# STC89C52RC.net
KiCad netlist of a schematic drawn in Altium Designer
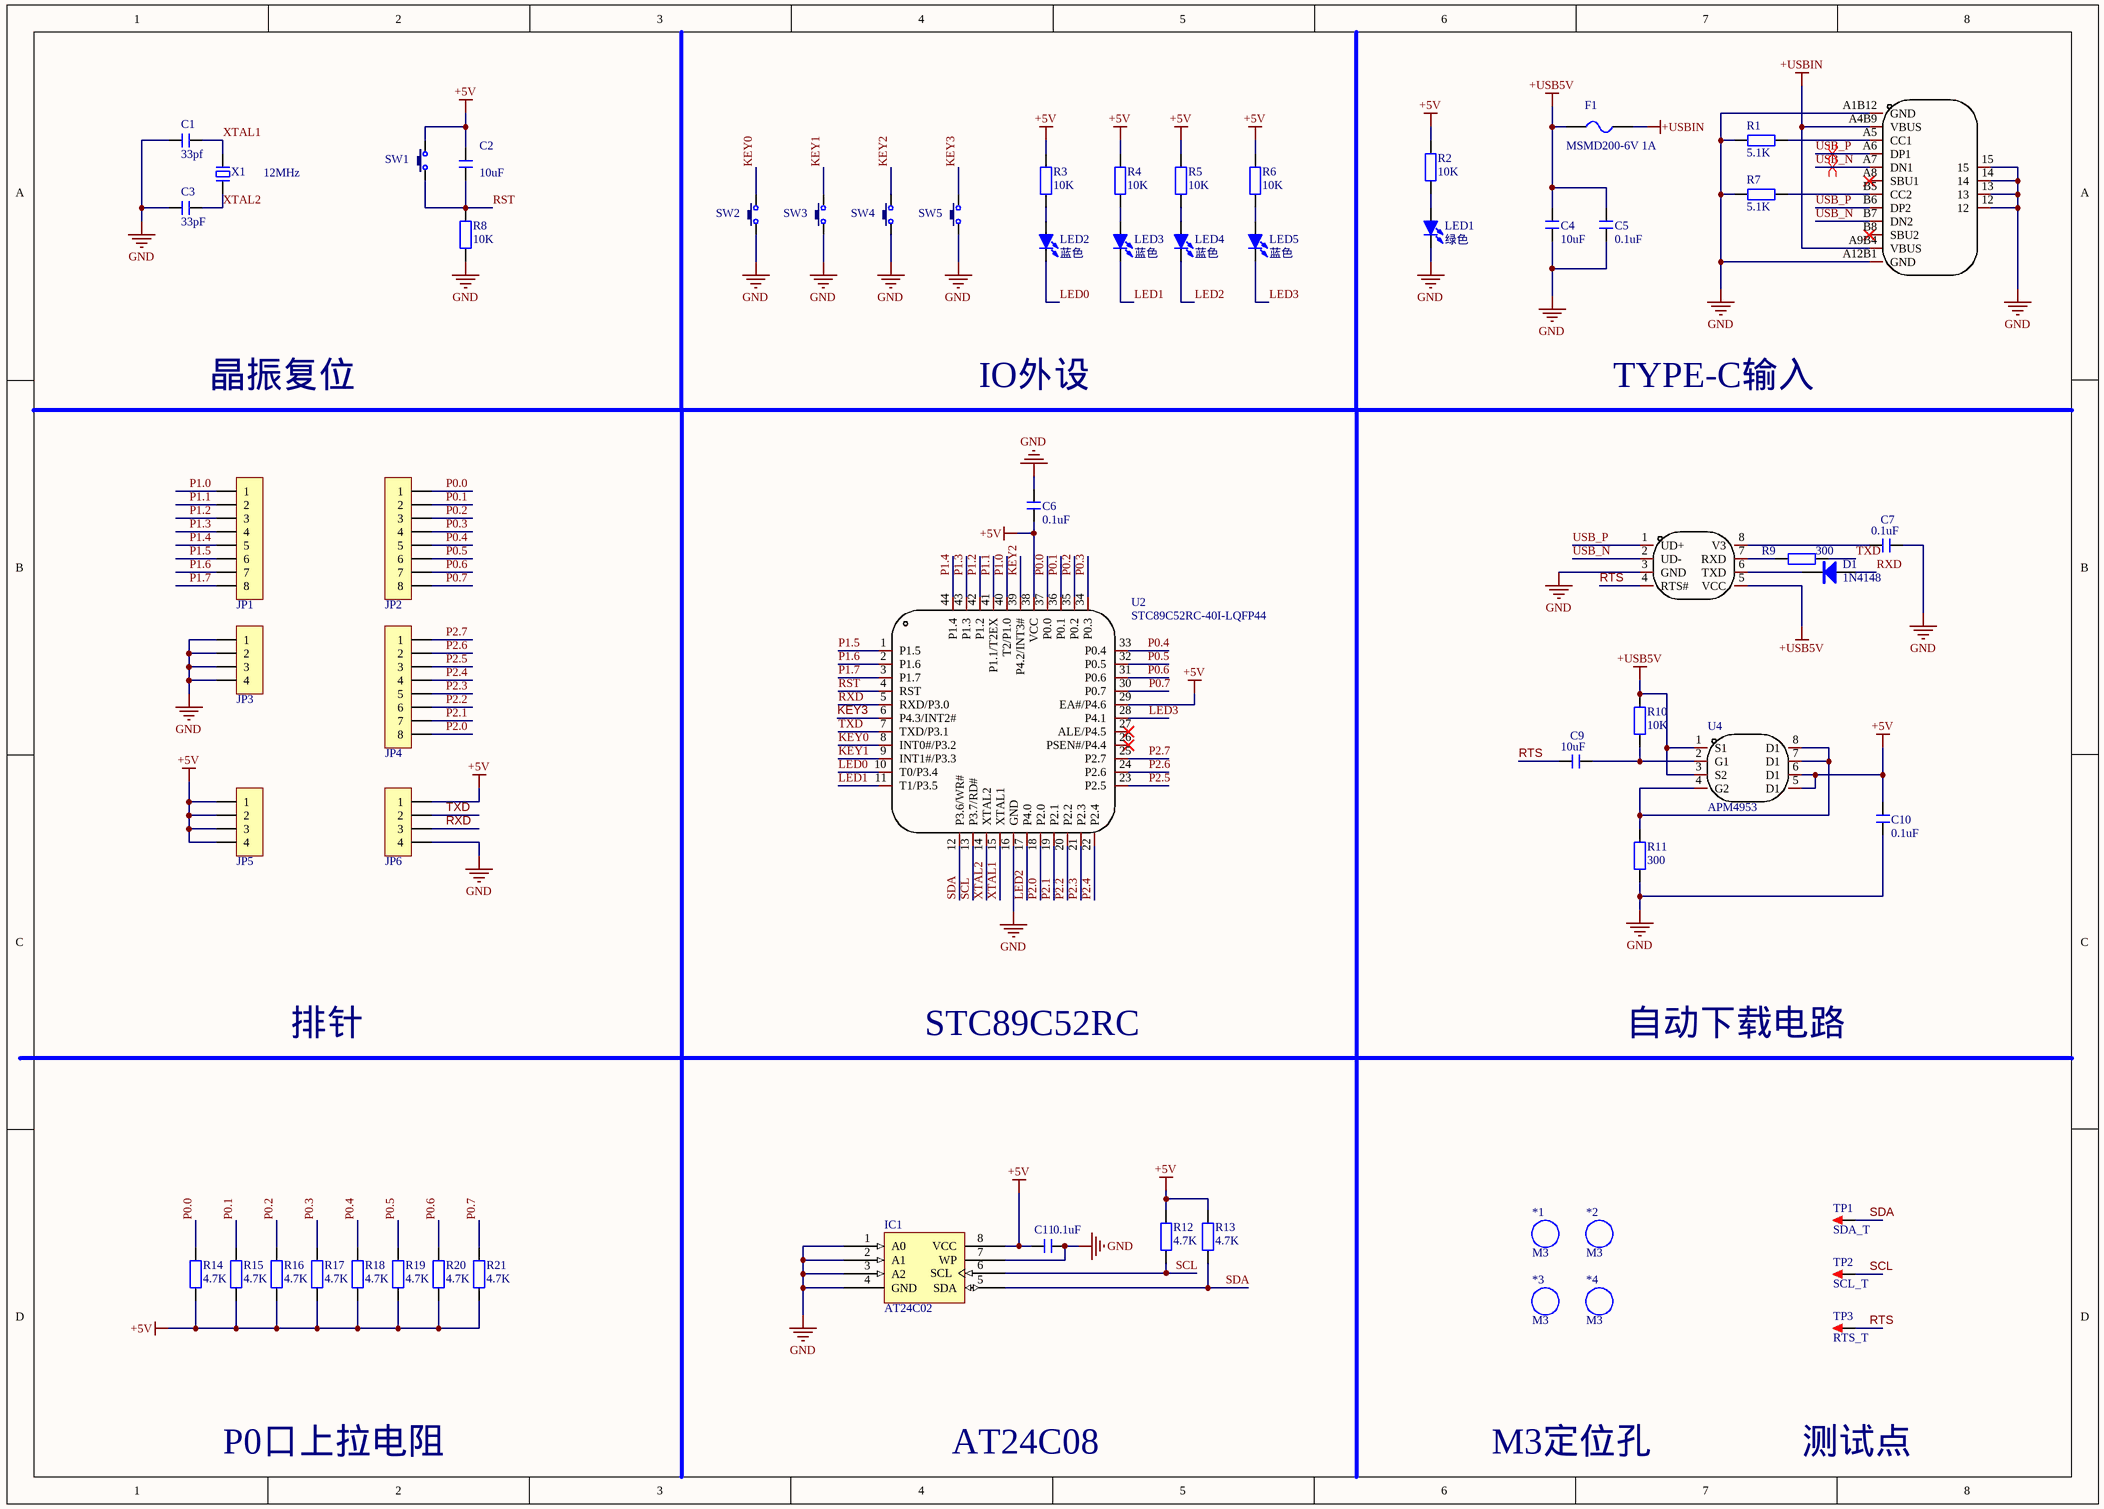
[diagram p0: STC89C52RC.SchDoc]

(export (version "E")
  (design (tool "Eeschema 10.0.6"))
  (components
    (comp (ref "*1")
      (value "M3")
      (footprint "M3 125X200")
      (description "铜柱孔")
      (fields (field (name "版权归属") "封装库来自淘宝 ID：黄晶宝石"))
      (libsource (lib "4.1 - 未分类器件") (part "M3"))
    )
    (comp (ref "*2")
      (value "M3")
      (footprint "M3 125X200")
      (description "铜柱孔")
      (fields (field (name "版权归属") "封装库来自淘宝 ID：黄晶宝石"))
      (libsource (lib "4.1 - 未分类器件") (part "M3"))
    )
    (comp (ref "*3")
      (value "M3")
      (footprint "M3 125X200")
      (description "铜柱孔")
      (fields (field (name "版权归属") "封装库来自淘宝 ID：黄晶宝石"))
      (libsource (lib "4.1 - 未分类器件") (part "M3"))
    )
    (comp (ref "*4")
      (value "M3")
      (footprint "M3 125X200")
      (description "铜柱孔")
      (fields (field (name "版权归属") "封装库来自淘宝 ID：黄晶宝石"))
      (libsource (lib "4.1 - 未分类器件") (part "M3"))
    )
    (comp (ref "C1")
      (value "33pf")
      (footprint "C 0805_L")
      (description "无极性贴片电容")
      (fields (field (name "版权归属") "源创客"))
      (libsource (lib "3.1   - 电阻-电容-电感") (part "C"))
    )
    (comp (ref "C2")
      (value "10uF")
      (footprint "C 0805_L")
      (description "无极性贴片电容")
      (fields (field (name "版权归属") "源创客"))
      (libsource (lib "3.1   - 电阻-电容-电感") (part "C"))
    )
    (comp (ref "C3")
      (value "33pF")
      (footprint "C 0805_L")
      (description "无极性贴片电容")
      (fields (field (name "版权归属") "源创客"))
      (libsource (lib "3.1   - 电阻-电容-电感") (part "C"))
    )
    (comp (ref "C4")
      (value "10uF")
      (footprint "C 0805_L")
      (description "无极性贴片电容")
      (fields (field (name "版权归属") "源创客"))
      (libsource (lib "3.1   - 电阻-电容-电感") (part "C"))
    )
    (comp (ref "C5")
      (value "0.1uF")
      (footprint "C 0805_L")
      (description "无极性贴片电容")
      (fields (field (name "版权归属") "源创客"))
      (libsource (lib "3.1   - 电阻-电容-电感") (part "C"))
    )
    (comp (ref "C6")
      (value "0.1uF")
      (footprint "C 0805_L")
      (description "无极性贴片电容")
      (fields (field (name "版权归属") "源创客"))
      (libsource (lib "3.1   - 电阻-电容-电感") (part "C"))
    )
    (comp (ref "C7")
      (value "0.1uF")
      (footprint "C 0805_L")
      (description "无极性贴片电容")
      (fields (field (name "版权归属") "源创客"))
      (libsource (lib "3.1   - 电阻-电容-电感") (part "C"))
    )
    (comp (ref "C9")
      (value "10uF")
      (footprint "C 0805_L")
      (description "无极性贴片电容")
      (fields (field (name "版权归属") "源创客"))
      (libsource (lib "3.1   - 电阻-电容-电感") (part "C"))
    )
    (comp (ref "C10")
      (value "0.1uF")
      (footprint "C 0805_L")
      (description "无极性贴片电容")
      (fields (field (name "版权归属") "源创客"))
      (libsource (lib "3.1   - 电阻-电容-电感") (part "C"))
    )
    (comp (ref "C11")
      (value "0.1uF")
      (footprint "C 0805_L")
      (description "无极性贴片电容")
      (fields (field (name "版权归属") "源创客"))
      (libsource (lib "3.1   - 电阻-电容-电感") (part "C"))
    )
    (comp (ref "D1")
      (value "1N4148")
      (footprint "SOD-323")
      (description "高速开关二极管")
      (fields (field (name "版权归属") "源创客"))
      (libsource (lib "8.1   - 二极管-整流桥") (part "1N4148"))
    )
    (comp (ref "F1")
      (value "MSMD200-6V 1A")
      (footprint "FU 0805")
      (description "贴片保险丝")
      (fields (field (name "版权归属") "封装库来自淘宝卖家 ID：黄晶宝石"))
      (libsource (lib "2.0 - 保险丝-晶振-光耦") (part "FU"))
    )
    (comp (ref "IC1")
      (value "AT24C02")
      (footprint "SOP8_N")
      (description "外置EEPROM")
      (fields (field (name "版权归属") "源创客"))
      (libsource (lib "1.1   - IC芯片") (part "24Cxx"))
    )
    (comp (ref "JP1")
      (value "HDR-1X8")
      (footprint "HDR2.54-LI-8P")
      (description "8P接插件")
      (fields (field (name "版权归属") "封装库来自淘宝 ID：黄晶宝石"))
      (libsource (lib "5.4 - 接插件-脚距2.54 (100mil) ") (part "Header 8"))
    )
    (comp (ref "JP2")
      (value "HDR-1X8")
      (footprint "HDR2.54-LI-8P")
      (description "8P接插件")
      (fields (field (name "版权归属") "封装库来自淘宝 ID：黄晶宝石"))
      (libsource (lib "") (part "Header 8_1"))
    )
    (comp (ref "JP3")
      (value "HDR-1X4")
      (footprint "HDR2.54-LI-4P")
      (description "4P接插件")
      (fields (field (name "版权归属") "封装库来自淘宝 ID：黄晶宝石"))
      (libsource (lib "") (part "Header 4_1"))
    )
    (comp (ref "JP4")
      (value "HDR-1X8")
      (footprint "HDR2.54-LI-8P")
      (description "8P接插件")
      (fields (field (name "版权归属") "封装库来自淘宝 ID：黄晶宝石"))
      (libsource (lib "") (part "Header 8_1"))
    )
    (comp (ref "JP5")
      (value "HDR-1X4")
      (footprint "HDR2.54-LI-4P")
      (description "4P接插件")
      (fields (field (name "版权归属") "封装库来自淘宝 ID：黄晶宝石"))
      (libsource (lib "") (part "Header 4_1"))
    )
    (comp (ref "JP6")
      (value "HDR-1X4")
      (footprint "HDR2.54-LI-4P")
      (description "4P接插件")
      (fields (field (name "版权归属") "封装库来自淘宝 ID：黄晶宝石"))
      (libsource (lib "5.4 - 接插件-脚距2.54 (100mil) ") (part "Header 4"))
    )
    (comp (ref "LED1")
      (value "绿色")
      (footprint "LED 0805G")
      (description "贴片LED")
      (fields (field (name "版权归属") "源创客"))
      (libsource (lib "9.1   - LED") (part "LED-SMD"))
    )
    (comp (ref "LED2")
      (value "蓝色")
      (footprint "LED 0805B")
      (description "贴片LED")
      (fields (field (name "版权归属") "源创客"))
      (libsource (lib "9.1   - LED") (part "LED-SMD"))
    )
    (comp (ref "LED3")
      (value "蓝色")
      (footprint "LED 0805B")
      (description "贴片LED")
      (fields (field (name "版权归属") "源创客"))
      (libsource (lib "9.1   - LED") (part "LED-SMD"))
    )
    (comp (ref "LED4")
      (value "蓝色")
      (footprint "LED 0805B")
      (description "贴片LED")
      (fields (field (name "版权归属") "源创客"))
      (libsource (lib "9.1   - LED") (part "LED-SMD"))
    )
    (comp (ref "LED5")
      (value "蓝色")
      (footprint "LED 0805B")
      (description "贴片LED")
      (fields (field (name "版权归属") "源创客"))
      (libsource (lib "9.1   - LED") (part "LED-SMD"))
    )
    (comp (ref "R1")
      (value "5.1K")
      (footprint "R 0805_L")
      (description "贴片电阻")
      (fields (field (name "版权归属") "源创客"))
      (libsource (lib "3.1   - 电阻-电容-电感") (part "R"))
    )
    (comp (ref "R2")
      (value "10K")
      (footprint "R 0805_L")
      (description "贴片电阻")
      (fields (field (name "版权归属") "源创客"))
      (libsource (lib "3.1   - 电阻-电容-电感") (part "R"))
    )
    (comp (ref "R3")
      (value "10K")
      (footprint "R 0805_L")
      (description "贴片电阻")
      (fields (field (name "版权归属") "源创客"))
      (libsource (lib "3.1   - 电阻-电容-电感") (part "R"))
    )
    (comp (ref "R4")
      (value "10K")
      (footprint "R 0805_L")
      (description "贴片电阻")
      (fields (field (name "版权归属") "源创客"))
      (libsource (lib "3.1   - 电阻-电容-电感") (part "R"))
    )
    (comp (ref "R5")
      (value "10K")
      (footprint "R 0805_L")
      (description "贴片电阻")
      (fields (field (name "版权归属") "源创客"))
      (libsource (lib "3.1   - 电阻-电容-电感") (part "R"))
    )
    (comp (ref "R6")
      (value "10K")
      (footprint "R 0805_L")
      (description "贴片电阻")
      (fields (field (name "版权归属") "源创客"))
      (libsource (lib "3.1   - 电阻-电容-电感") (part "R"))
    )
    (comp (ref "R7")
      (value "5.1K")
      (footprint "R 0805_L")
      (description "贴片电阻")
      (fields (field (name "版权归属") "源创客"))
      (libsource (lib "3.1   - 电阻-电容-电感") (part "R"))
    )
    (comp (ref "R8")
      (value "10K")
      (footprint "R 0805_L")
      (description "贴片电阻")
      (fields (field (name "版权归属") "源创客"))
      (libsource (lib "3.1   - 电阻-电容-电感") (part "R"))
    )
    (comp (ref "R9")
      (value "300")
      (footprint "R 0805_L")
      (description "贴片电阻")
      (fields (field (name "版权归属") "源创客"))
      (libsource (lib "3.1   - 电阻-电容-电感") (part "R"))
    )
    (comp (ref "R10")
      (value "10K")
      (footprint "R 0805_L")
      (description "贴片电阻")
      (fields (field (name "版权归属") "源创客"))
      (libsource (lib "3.1   - 电阻-电容-电感") (part "R"))
    )
    (comp (ref "R11")
      (value "300")
      (footprint "R 0805_L")
      (description "贴片电阻")
      (fields (field (name "版权归属") "源创客"))
      (libsource (lib "3.1   - 电阻-电容-电感") (part "R"))
    )
    (comp (ref "R12")
      (value "4.7K")
      (footprint "R 0805_L")
      (description "贴片电阻")
      (fields (field (name "版权归属") "源创客"))
      (libsource (lib "3.1   - 电阻-电容-电感") (part "R"))
    )
    (comp (ref "R13")
      (value "4.7K")
      (footprint "R 0805_L")
      (description "贴片电阻")
      (fields (field (name "版权归属") "源创客"))
      (libsource (lib "3.1   - 电阻-电容-电感") (part "R"))
    )
    (comp (ref "R14")
      (value "4.7K")
      (footprint "R 0805_L")
      (description "贴片电阻")
      (fields (field (name "版权归属") "源创客"))
      (libsource (lib "3.1   - 电阻-电容-电感") (part "R"))
    )
    (comp (ref "R15")
      (value "4.7K")
      (footprint "R 0805_L")
      (description "贴片电阻")
      (fields (field (name "版权归属") "源创客"))
      (libsource (lib "3.1   - 电阻-电容-电感") (part "R"))
    )
    (comp (ref "R16")
      (value "4.7K")
      (footprint "R 0805_L")
      (description "贴片电阻")
      (fields (field (name "版权归属") "源创客"))
      (libsource (lib "3.1   - 电阻-电容-电感") (part "R"))
    )
    (comp (ref "R17")
      (value "4.7K")
      (footprint "R 0805_L")
      (description "贴片电阻")
      (fields (field (name "版权归属") "源创客"))
      (libsource (lib "3.1   - 电阻-电容-电感") (part "R"))
    )
    (comp (ref "R18")
      (value "4.7K")
      (footprint "R 0805_L")
      (description "贴片电阻")
      (fields (field (name "版权归属") "源创客"))
      (libsource (lib "3.1   - 电阻-电容-电感") (part "R"))
    )
    (comp (ref "R19")
      (value "4.7K")
      (footprint "R 0805_L")
      (description "贴片电阻")
      (fields (field (name "版权归属") "源创客"))
      (libsource (lib "3.1   - 电阻-电容-电感") (part "R"))
    )
    (comp (ref "R20")
      (value "4.7K")
      (footprint "R 0805_L")
      (description "贴片电阻")
      (fields (field (name "版权归属") "源创客"))
      (libsource (lib "3.1   - 电阻-电容-电感") (part "R"))
    )
    (comp (ref "R21")
      (value "4.7K")
      (footprint "R 0805_L")
      (description "贴片电阻")
      (fields (field (name "版权归属") "源创客"))
      (libsource (lib "3.1   - 电阻-电容-电感") (part "R"))
    )
    (comp (ref "SW1")
      (value "3x6x5")
      (footprint "TSW SMD-3*6*2.5")
      (description "3x6轻触开关")
      (fields (field (name "版权归属") "源创客"))
      (libsource (lib "5.1   - 按键-开关") (part "TSW 3x6"))
    )
    (comp (ref "SW2")
      (value "3x6x5")
      (footprint "TSW SMD-3*6*2.5")
      (description "3x6轻触开关")
      (fields (field (name "版权归属") "源创客"))
      (libsource (lib "5.1   - 按键-开关") (part "TSW 3x6"))
    )
    (comp (ref "SW3")
      (value "3x6x5")
      (footprint "TSW SMD-3*6*2.5")
      (description "3x6轻触开关")
      (fields (field (name "版权归属") "源创客"))
      (libsource (lib "5.1   - 按键-开关") (part "TSW 3x6"))
    )
    (comp (ref "SW4")
      (value "3x6x5")
      (footprint "TSW SMD-3*6*2.5")
      (description "3x6轻触开关")
      (fields (field (name "版权归属") "源创客"))
      (libsource (lib "5.1   - 按键-开关") (part "TSW 3x6"))
    )
    (comp (ref "SW5")
      (value "3x6x5")
      (footprint "TSW SMD-3*6*2.5")
      (description "3x6轻触开关")
      (fields (field (name "版权归属") "源创客"))
      (libsource (lib "5.1   - 按键-开关") (part "TSW 3x6"))
    )
    (comp (ref "TP1")
      (value "SDA_T")
      (footprint "TEST 1.2")
      (description "测试点")
      (fields (field (name "版权归属") "封装库来自淘宝 ID：黄晶宝石"))
      (libsource (lib "4.1 - 未分类器件") (part "TEST"))
    )
    (comp (ref "TP2")
      (value "SCL_T")
      (footprint "TEST 1.2")
      (description "测试点")
      (fields (field (name "版权归属") "封装库来自淘宝 ID：黄晶宝石"))
      (libsource (lib "4.1 - 未分类器件") (part "TEST"))
    )
    (comp (ref "TP3")
      (value "RTS_T")
      (footprint "TEST 1.2")
      (description "测试点")
      (fields (field (name "版权归属") "封装库来自淘宝 ID：黄晶宝石"))
      (libsource (lib "4.1 - 未分类器件") (part "TEST"))
    )
    (comp (ref "U1")
      (value "YTC-TC16S-24")
      (footprint "USB-C-SMD_YTC-TC16S-24")
      (fields (field (name "MANUFACTURER") "YIYUAN(怡远)"))
      (libsource (lib "Type-C16S-24") (part "YTC-TC16S-24"))
    )
    (comp (ref "U2")
      (value "STC89C52RC")
      (footprint "LQFP44 10X10_N")
      (description "CPU内核:51系列;CPU最大主频:-;程序存储容量:8KB;程序存储器类型:FLASH;RAM总容量:512Byte;GPIO端口数量:39;")
      (fields
        (field (name "NAME") "STC89C52RC-40I-LQFP44")
        (field (name "MANUFACTURER") "STC(宏晶)")
        (field (name "MANUFACTURER PART") "STC89C52RC-40I-LQFP44")
      )
      (libsource (lib "altium-import") (part "root_0_STC89C52RC-40I-LQFP44_"))
    )
    (comp (ref "U3")
      (value "CH340N")
      (footprint "SOP8_L")
      (fields (field (name "MANUFACTURER") "WCH(南京沁恒)"))
      (libsource (lib "CH340N") (part "CH340N"))
    )
    (comp (ref "U4")
      (value "APM4953")
      (footprint "SOP8")
      (description "场效应管")
      (libsource (lib "STC89C52RC") (part "APM4953"))
    )
    (comp (ref "X1")
      (value "12MHz")
      (footprint "OSC 5032-2P")
      (description "2脚无源脚晶振")
      (fields (field (name "版权归属") "源创客"))
      (libsource (lib "10.1 - 保险丝-晶振") (part "XTAL-2P"))
    )
  )
  (nets
    (net (code "1") (name "+5V") (class "Default")
      (node (ref "C10") (pin "1") (pinfunction "1_1") (pintype "passive"))
      (node (ref "C11") (pin "1") (pinfunction "1_1") (pintype "passive"))
      (node (ref "C2") (pin "1") (pinfunction "1_1") (pintype "passive"))
      (node (ref "C6") (pin "2") (pinfunction "2_2") (pintype "passive"))
      (node (ref "IC1") (pin "8") (pinfunction "VCC_8") (pintype "power_in"))
      (node (ref "JP5") (pin "1") (pinfunction "1_1") (pintype "passive"))
      (node (ref "JP5") (pin "2") (pinfunction "2_2") (pintype "passive"))
      (node (ref "JP5") (pin "3") (pinfunction "3_3") (pintype "passive"))
      (node (ref "JP5") (pin "4") (pinfunction "4_4") (pintype "passive"))
      (node (ref "JP6") (pin "1") (pinfunction "1_1") (pintype "passive"))
      (node (ref "R12") (pin "2") (pinfunction "2_2") (pintype "passive"))
      (node (ref "R13") (pin "2") (pinfunction "2_2") (pintype "passive"))
      (node (ref "R14") (pin "1") (pinfunction "1_1") (pintype "passive"))
      (node (ref "R15") (pin "1") (pinfunction "1_1") (pintype "passive"))
      (node (ref "R16") (pin "1") (pinfunction "1_1") (pintype "passive"))
      (node (ref "R17") (pin "1") (pinfunction "1_1") (pintype "passive"))
      (node (ref "R18") (pin "1") (pinfunction "1_1") (pintype "passive"))
      (node (ref "R19") (pin "1") (pinfunction "1_1") (pintype "passive"))
      (node (ref "R2") (pin "2") (pinfunction "2_2") (pintype "passive"))
      (node (ref "R20") (pin "1") (pinfunction "1_1") (pintype "passive"))
      (node (ref "R21") (pin "1") (pinfunction "1_1") (pintype "passive"))
      (node (ref "R3") (pin "2") (pinfunction "2_2") (pintype "passive"))
      (node (ref "R4") (pin "2") (pinfunction "2_2") (pintype "passive"))
      (node (ref "R5") (pin "2") (pinfunction "2_2") (pintype "passive"))
      (node (ref "R6") (pin "2") (pinfunction "2_2") (pintype "passive"))
      (node (ref "SW1") (pin "2") (pinfunction "2_2") (pintype "passive"))
      (node (ref "U2") (pin "29") (pinfunction "EA#/P4.6_29") (pintype "passive"))
      (node (ref "U2") (pin "38") (pinfunction "VCC_38") (pintype "passive"))
      (node (ref "U4") (pin "5") (pinfunction "D1_5") (pintype "passive"))
      (node (ref "U4") (pin "6") (pinfunction "D1_6") (pintype "passive"))
    )
    (net (code "2") (name "+USB5V") (class "Default")
      (node (ref "C4") (pin "2") (pinfunction "2_2") (pintype "passive"))
      (node (ref "C5") (pin "2") (pinfunction "2_2") (pintype "passive"))
      (node (ref "F1") (pin "1") (pinfunction "1_1") (pintype "passive"))
      (node (ref "R10") (pin "2") (pinfunction "2_2") (pintype "passive"))
      (node (ref "U3") (pin "5") (pinfunction "VCC_5") (pintype "passive"))
      (node (ref "U4") (pin "1") (pinfunction "S1_1") (pintype "passive"))
      (node (ref "U4") (pin "3") (pinfunction "S2_3") (pintype "passive"))
    )
    (net (code "3") (name "+USBIN") (class "Default")
      (node (ref "F1") (pin "2") (pinfunction "2_2") (pintype "passive"))
      (node (ref "U1") (pin "A4B9") (pinfunction "VBUS_A4B9") (pintype "passive"))
      (node (ref "U1") (pin "A9B4") (pinfunction "VBUS_A9B4") (pintype "passive"))
    )
    (net (code "4") (name "/KEY0") (class "Default")
      (node (ref "SW2") (pin "2") (pinfunction "2_2") (pintype "passive"))
      (node (ref "U2") (pin "8") (pinfunction "INT0#/P3.2_8") (pintype "passive"))
    )
    (net (code "5") (name "/KEY1") (class "Default")
      (node (ref "SW3") (pin "2") (pinfunction "2_2") (pintype "passive"))
      (node (ref "U2") (pin "9") (pinfunction "INT1#/P3.3_9") (pintype "passive"))
    )
    (net (code "6") (name "/KEY2") (class "Default")
      (node (ref "SW4") (pin "2") (pinfunction "2_2") (pintype "passive"))
      (node (ref "U2") (pin "39") (pinfunction "P4.2/INT3#_39") (pintype "passive"))
    )
    (net (code "7") (name "/KEY3") (class "Default")
      (node (ref "SW5") (pin "2") (pinfunction "2_2") (pintype "passive"))
      (node (ref "U2") (pin "6") (pinfunction "P4.3/INT2#_6") (pintype "passive"))
    )
    (net (code "8") (name "/LED0") (class "Default")
      (node (ref "LED2") (pin "2") (pinfunction "K_2") (pintype "passive"))
      (node (ref "U2") (pin "10") (pinfunction "T0/P3.4_10") (pintype "passive"))
    )
    (net (code "9") (name "/LED1") (class "Default")
      (node (ref "LED3") (pin "2") (pinfunction "K_2") (pintype "passive"))
      (node (ref "U2") (pin "11") (pinfunction "T1/P3.5_11") (pintype "passive"))
    )
    (net (code "10") (name "/LED2") (class "Default")
      (node (ref "LED4") (pin "2") (pinfunction "K_2") (pintype "passive"))
      (node (ref "U2") (pin "17") (pinfunction "P4.0_17") (pintype "passive"))
    )
    (net (code "11") (name "/LED3") (class "Default")
      (node (ref "LED5") (pin "2") (pinfunction "K_2") (pintype "passive"))
      (node (ref "U2") (pin "28") (pinfunction "P4.1_28") (pintype "passive"))
    )
    (net (code "12") (name "/P0.0") (class "Default")
      (node (ref "JP2") (pin "1") (pinfunction "1_1") (pintype "passive"))
      (node (ref "R14") (pin "2") (pinfunction "2_2") (pintype "passive"))
      (node (ref "U2") (pin "37") (pinfunction "P0.0_37") (pintype "passive"))
    )
    (net (code "13") (name "/P0.1") (class "Default")
      (node (ref "JP2") (pin "2") (pinfunction "2_2") (pintype "passive"))
      (node (ref "R15") (pin "2") (pinfunction "2_2") (pintype "passive"))
      (node (ref "U2") (pin "36") (pinfunction "P0.1_36") (pintype "passive"))
    )
    (net (code "14") (name "/P0.2") (class "Default")
      (node (ref "JP2") (pin "3") (pinfunction "3_3") (pintype "passive"))
      (node (ref "R16") (pin "2") (pinfunction "2_2") (pintype "passive"))
      (node (ref "U2") (pin "35") (pinfunction "P0.2_35") (pintype "passive"))
    )
    (net (code "15") (name "/P0.3") (class "Default")
      (node (ref "JP2") (pin "4") (pinfunction "4_4") (pintype "passive"))
      (node (ref "R17") (pin "2") (pinfunction "2_2") (pintype "passive"))
      (node (ref "U2") (pin "34") (pinfunction "P0.3_34") (pintype "passive"))
    )
    (net (code "16") (name "/P0.4") (class "Default")
      (node (ref "JP2") (pin "5") (pinfunction "5_5") (pintype "passive"))
      (node (ref "R18") (pin "2") (pinfunction "2_2") (pintype "passive"))
      (node (ref "U2") (pin "33") (pinfunction "P0.4_33") (pintype "passive"))
    )
    (net (code "17") (name "/P0.5") (class "Default")
      (node (ref "JP2") (pin "6") (pinfunction "6_6") (pintype "passive"))
      (node (ref "R19") (pin "2") (pinfunction "2_2") (pintype "passive"))
      (node (ref "U2") (pin "32") (pinfunction "P0.5_32") (pintype "passive"))
    )
    (net (code "18") (name "/P0.6") (class "Default")
      (node (ref "JP2") (pin "7") (pinfunction "7_7") (pintype "passive"))
      (node (ref "R20") (pin "2") (pinfunction "2_2") (pintype "passive"))
      (node (ref "U2") (pin "31") (pinfunction "P0.6_31") (pintype "passive"))
    )
    (net (code "19") (name "/P0.7") (class "Default")
      (node (ref "JP2") (pin "8") (pinfunction "8_8") (pintype "passive"))
      (node (ref "R21") (pin "2") (pinfunction "2_2") (pintype "passive"))
      (node (ref "U2") (pin "30") (pinfunction "P0.7_30") (pintype "passive"))
    )
    (net (code "20") (name "/P1.0") (class "Default")
      (node (ref "JP1") (pin "1") (pinfunction "1_1") (pintype "passive"))
      (node (ref "U2") (pin "40") (pinfunction "T2/P1.0_40") (pintype "passive"))
    )
    (net (code "21") (name "/P1.1") (class "Default")
      (node (ref "JP1") (pin "2") (pinfunction "2_2") (pintype "passive"))
      (node (ref "U2") (pin "41") (pinfunction "P1.1/T2EX_41") (pintype "passive"))
    )
    (net (code "22") (name "/P1.2") (class "Default")
      (node (ref "JP1") (pin "3") (pinfunction "3_3") (pintype "passive"))
      (node (ref "U2") (pin "42") (pinfunction "P1.2_42") (pintype "passive"))
    )
    (net (code "23") (name "/P1.3") (class "Default")
      (node (ref "JP1") (pin "4") (pinfunction "4_4") (pintype "passive"))
      (node (ref "U2") (pin "43") (pinfunction "P1.3_43") (pintype "passive"))
    )
    (net (code "24") (name "/P1.4") (class "Default")
      (node (ref "JP1") (pin "5") (pinfunction "5_5") (pintype "passive"))
      (node (ref "U2") (pin "44") (pinfunction "P1.4_44") (pintype "passive"))
    )
    (net (code "25") (name "/P1.5") (class "Default")
      (node (ref "JP1") (pin "6") (pinfunction "6_6") (pintype "passive"))
      (node (ref "U2") (pin "1") (pinfunction "P1.5_1") (pintype "passive"))
    )
    (net (code "26") (name "/P1.6") (class "Default")
      (node (ref "JP1") (pin "7") (pinfunction "7_7") (pintype "passive"))
      (node (ref "U2") (pin "2") (pinfunction "P1.6_2") (pintype "passive"))
    )
    (net (code "27") (name "/P1.7") (class "Default")
      (node (ref "JP1") (pin "8") (pinfunction "8_8") (pintype "passive"))
      (node (ref "U2") (pin "3") (pinfunction "P1.7_3") (pintype "passive"))
    )
    (net (code "28") (name "/P2.0") (class "Default")
      (node (ref "JP4") (pin "8") (pinfunction "8_8") (pintype "passive"))
      (node (ref "U2") (pin "18") (pinfunction "P2.0_18") (pintype "passive"))
    )
    (net (code "29") (name "/P2.1") (class "Default")
      (node (ref "JP4") (pin "7") (pinfunction "7_7") (pintype "passive"))
      (node (ref "U2") (pin "19") (pinfunction "P2.1_19") (pintype "passive"))
    )
    (net (code "30") (name "/P2.2") (class "Default")
      (node (ref "JP4") (pin "6") (pinfunction "6_6") (pintype "passive"))
      (node (ref "U2") (pin "20") (pinfunction "P2.2_20") (pintype "passive"))
    )
    (net (code "31") (name "/P2.3") (class "Default")
      (node (ref "JP4") (pin "5") (pinfunction "5_5") (pintype "passive"))
      (node (ref "U2") (pin "21") (pinfunction "P2.3_21") (pintype "passive"))
    )
    (net (code "32") (name "/P2.4") (class "Default")
      (node (ref "JP4") (pin "4") (pinfunction "4_4") (pintype "passive"))
      (node (ref "U2") (pin "22") (pinfunction "P2.4_22") (pintype "passive"))
    )
    (net (code "33") (name "/P2.5") (class "Default")
      (node (ref "JP4") (pin "3") (pinfunction "3_3") (pintype "passive"))
      (node (ref "U2") (pin "23") (pinfunction "P2.5_23") (pintype "passive"))
    )
    (net (code "34") (name "/P2.6") (class "Default")
      (node (ref "JP4") (pin "2") (pinfunction "2_2") (pintype "passive"))
      (node (ref "U2") (pin "24") (pinfunction "P2.6_24") (pintype "passive"))
    )
    (net (code "35") (name "/P2.7") (class "Default")
      (node (ref "JP4") (pin "1") (pinfunction "1_1") (pintype "passive"))
      (node (ref "U2") (pin "25") (pinfunction "P2.7_25") (pintype "passive"))
    )
    (net (code "36") (name "/RST") (class "Default")
      (node (ref "C2") (pin "2") (pinfunction "2_2") (pintype "passive"))
      (node (ref "R8") (pin "2") (pinfunction "2_2") (pintype "passive"))
      (node (ref "SW1") (pin "1") (pinfunction "1_1") (pintype "passive"))
      (node (ref "U2") (pin "4") (pinfunction "RST_4") (pintype "passive"))
    )
    (net (code "37") (name "/RTS") (class "Default")
      (node (ref "C9") (pin "1") (pinfunction "1_1") (pintype "passive"))
      (node (ref "TP3") (pin "1") (pinfunction "1_1") (pintype "passive"))
      (node (ref "U3") (pin "4") (pinfunction "RTS#_4") (pintype "passive"))
    )
    (net (code "38") (name "/RXD") (class "Default")
      (node (ref "D1") (pin "1") (pinfunction "A_1") (pintype "passive"))
      (node (ref "JP6") (pin "3") (pinfunction "3_3") (pintype "passive"))
      (node (ref "U2") (pin "5") (pinfunction "RXD/P3.0_5") (pintype "passive"))
    )
    (net (code "39") (name "/SCL") (class "Default")
      (node (ref "IC1") (pin "6") (pinfunction "SCL_6") (pintype "input"))
      (node (ref "R12") (pin "1") (pinfunction "1_1") (pintype "passive"))
      (node (ref "TP2") (pin "1") (pinfunction "1_1") (pintype "passive"))
      (node (ref "U2") (pin "13") (pinfunction "P3.7/RD#_13") (pintype "passive"))
    )
    (net (code "40") (name "/SDA") (class "Default")
      (node (ref "IC1") (pin "5") (pinfunction "SDA_5") (pintype "bidirectional"))
      (node (ref "R13") (pin "1") (pinfunction "1_1") (pintype "passive"))
      (node (ref "TP1") (pin "1") (pinfunction "1_1") (pintype "passive"))
      (node (ref "U2") (pin "12") (pinfunction "P3.6/WR#_12") (pintype "passive"))
    )
    (net (code "41") (name "/TXD") (class "Default")
      (node (ref "JP6") (pin "2") (pinfunction "2_2") (pintype "passive"))
      (node (ref "R9") (pin "2") (pinfunction "2_2") (pintype "passive"))
      (node (ref "U2") (pin "7") (pinfunction "TXD/P3.1_7") (pintype "passive"))
    )
    (net (code "42") (name "/USB_N") (class "Default")
      (node (ref "U1") (pin "A7") (pinfunction "DN1_A7") (pintype "passive"))
      (node (ref "U1") (pin "B7") (pinfunction "DN2_B7") (pintype "passive"))
      (node (ref "U3") (pin "2") (pinfunction "UD-_2") (pintype "passive"))
    )
    (net (code "43") (name "/USB_P") (class "Default")
      (node (ref "U1") (pin "A6") (pinfunction "DP1_A6") (pintype "passive"))
      (node (ref "U1") (pin "B6") (pinfunction "DP2_B6") (pintype "passive"))
      (node (ref "U3") (pin "1") (pinfunction "UD+_1") (pintype "passive"))
    )
    (net (code "44") (name "/XTAL1") (class "Default")
      (node (ref "C1") (pin "1") (pinfunction "1_1") (pintype "passive"))
      (node (ref "U2") (pin "15") (pinfunction "XTAL1_15") (pintype "passive"))
      (node (ref "X1") (pin "1") (pinfunction "1_1") (pintype "passive"))
    )
    (net (code "45") (name "/XTAL2") (class "Default")
      (node (ref "C3") (pin "1") (pinfunction "1_1") (pintype "passive"))
      (node (ref "U2") (pin "14") (pinfunction "XTAL2_14") (pintype "passive"))
      (node (ref "X1") (pin "2") (pinfunction "2_2") (pintype "passive"))
    )
    (net (code "46") (name "GND") (class "Default")
      (node (ref "C1") (pin "2") (pinfunction "2_2") (pintype "passive"))
      (node (ref "C10") (pin "2") (pinfunction "2_2") (pintype "passive"))
      (node (ref "C11") (pin "2") (pinfunction "2_2") (pintype "passive"))
      (node (ref "C3") (pin "2") (pinfunction "2_2") (pintype "passive"))
      (node (ref "C4") (pin "1") (pinfunction "1_1") (pintype "passive"))
      (node (ref "C5") (pin "1") (pinfunction "1_1") (pintype "passive"))
      (node (ref "C6") (pin "1") (pinfunction "1_1") (pintype "passive"))
      (node (ref "C7") (pin "2") (pinfunction "2_2") (pintype "passive"))
      (node (ref "IC1") (pin "1") (pinfunction "A0_1") (pintype "input"))
      (node (ref "IC1") (pin "2") (pinfunction "A1_2") (pintype "input"))
      (node (ref "IC1") (pin "3") (pinfunction "A2_3") (pintype "input"))
      (node (ref "IC1") (pin "4") (pinfunction "GND_4") (pintype "passive"))
      (node (ref "IC1") (pin "7") (pinfunction "WP_7") (pintype "passive"))
      (node (ref "JP3") (pin "1") (pinfunction "1_1") (pintype "passive"))
      (node (ref "JP3") (pin "2") (pinfunction "2_2") (pintype "passive"))
      (node (ref "JP3") (pin "3") (pinfunction "3_3") (pintype "passive"))
      (node (ref "JP3") (pin "4") (pinfunction "4_4") (pintype "passive"))
      (node (ref "JP6") (pin "4") (pinfunction "4_4") (pintype "passive"))
      (node (ref "LED1") (pin "2") (pinfunction "K_2") (pintype "passive"))
      (node (ref "R1") (pin "1") (pinfunction "1_1") (pintype "passive"))
      (node (ref "R11") (pin "1") (pinfunction "1_1") (pintype "passive"))
      (node (ref "R7") (pin "1") (pinfunction "1_1") (pintype "passive"))
      (node (ref "R8") (pin "1") (pinfunction "1_1") (pintype "passive"))
      (node (ref "SW2") (pin "1") (pinfunction "1_1") (pintype "passive"))
      (node (ref "SW3") (pin "1") (pinfunction "1_1") (pintype "passive"))
      (node (ref "SW4") (pin "1") (pinfunction "1_1") (pintype "passive"))
      (node (ref "SW5") (pin "1") (pinfunction "1_1") (pintype "passive"))
      (node (ref "U1") (pin "12") (pinfunction "12_12") (pintype "passive"))
      (node (ref "U1") (pin "13") (pinfunction "13_13") (pintype "passive"))
      (node (ref "U1") (pin "14") (pinfunction "14_14") (pintype "passive"))
      (node (ref "U1") (pin "15") (pinfunction "15_15") (pintype "passive"))
      (node (ref "U1") (pin "A12B1") (pinfunction "GND_A12B1") (pintype "passive"))
      (node (ref "U1") (pin "A1B12") (pinfunction "GND_A1B12") (pintype "passive"))
      (node (ref "U2") (pin "16") (pinfunction "GND_16") (pintype "passive"))
      (node (ref "U3") (pin "3") (pinfunction "GND_3") (pintype "passive"))
    )
    (net (code "47") (name "Net-(D1-K)") (class "Default")
      (node (ref "D1") (pin "2") (pinfunction "K_2") (pintype "passive"))
      (node (ref "U3") (pin "6") (pinfunction "TXD_6") (pintype "passive"))
    )
    (net (code "48") (name "Net-(LED1-A)") (class "Default")
      (node (ref "LED1") (pin "1") (pinfunction "A_1") (pintype "passive"))
      (node (ref "R2") (pin "1") (pinfunction "1_1") (pintype "passive"))
    )
    (net (code "49") (name "Net-(LED2-A)") (class "Default")
      (node (ref "LED2") (pin "1") (pinfunction "A_1") (pintype "passive"))
      (node (ref "R3") (pin "1") (pinfunction "1_1") (pintype "passive"))
    )
    (net (code "50") (name "Net-(LED3-A)") (class "Default")
      (node (ref "LED3") (pin "1") (pinfunction "A_1") (pintype "passive"))
      (node (ref "R4") (pin "1") (pinfunction "1_1") (pintype "passive"))
    )
    (net (code "51") (name "Net-(LED4-A)") (class "Default")
      (node (ref "LED4") (pin "1") (pinfunction "A_1") (pintype "passive"))
      (node (ref "R5") (pin "1") (pinfunction "1_1") (pintype "passive"))
    )
    (net (code "52") (name "Net-(LED5-A)") (class "Default")
      (node (ref "LED5") (pin "1") (pinfunction "A_1") (pintype "passive"))
      (node (ref "R6") (pin "1") (pinfunction "1_1") (pintype "passive"))
    )
    (net (code "53") (name "Net-(U1-CC1)") (class "Default")
      (node (ref "R1") (pin "2") (pinfunction "2_2") (pintype "passive"))
      (node (ref "U1") (pin "A5") (pinfunction "CC1_A5") (pintype "passive"))
    )
    (net (code "54") (name "Net-(U1-CC2)") (class "Default")
      (node (ref "R7") (pin "2") (pinfunction "2_2") (pintype "passive"))
      (node (ref "U1") (pin "B5") (pinfunction "CC2_B5") (pintype "passive"))
    )
    (net (code "55") (name "Net-(U3-RXD)") (class "Default")
      (node (ref "R9") (pin "1") (pinfunction "1_1") (pintype "passive"))
      (node (ref "U3") (pin "7") (pinfunction "RXD_7") (pintype "passive"))
    )
    (net (code "56") (name "Net-(U3-V3)") (class "Default")
      (node (ref "C7") (pin "1") (pinfunction "1_1") (pintype "passive"))
      (node (ref "U3") (pin "8") (pinfunction "V3_8") (pintype "passive"))
    )
    (net (code "57") (name "Net-(U4-G1)") (class "Default")
      (node (ref "C9") (pin "2") (pinfunction "2_2") (pintype "passive"))
      (node (ref "R10") (pin "1") (pinfunction "1_1") (pintype "passive"))
      (node (ref "U4") (pin "2") (pinfunction "G1_2") (pintype "passive"))
    )
    (net (code "58") (name "Net-(U4-G2)") (class "Default")
      (node (ref "R11") (pin "2") (pinfunction "2_2") (pintype "passive"))
      (node (ref "U4") (pin "4") (pinfunction "G2_4") (pintype "passive"))
      (node (ref "U4") (pin "7") (pinfunction "D1_7") (pintype "passive"))
      (node (ref "U4") (pin "8") (pinfunction "D1_8") (pintype "passive"))
    )
    (net (code "59") (name "unconnected-(U1-SBU1-PadA8)") (class "Default")
      (node (ref "U1") (pin "A8") (pinfunction "SBU1_A8") (pintype "passive+no_connect"))
    )
    (net (code "60") (name "unconnected-(U1-SBU2-PadB8)") (class "Default")
      (node (ref "U1") (pin "B8") (pinfunction "SBU2_B8") (pintype "passive+no_connect"))
    )
    (net (code "61") (name "unconnected-(U2-ALE{slash}P4.5-Pad27)") (class "Default")
      (node (ref "U2") (pin "27") (pinfunction "ALE/P4.5_27") (pintype "passive+no_connect"))
    )
    (net (code "62") (name "unconnected-(U2-PSEN#{slash}P4.4-Pad26)") (class "Default")
      (node (ref "U2") (pin "26") (pinfunction "PSEN#/P4.4_26") (pintype "passive+no_connect"))
    )
  )
)
